# generic_midi_1.net
KiCad netlist of a schematic drawn in EAGLE
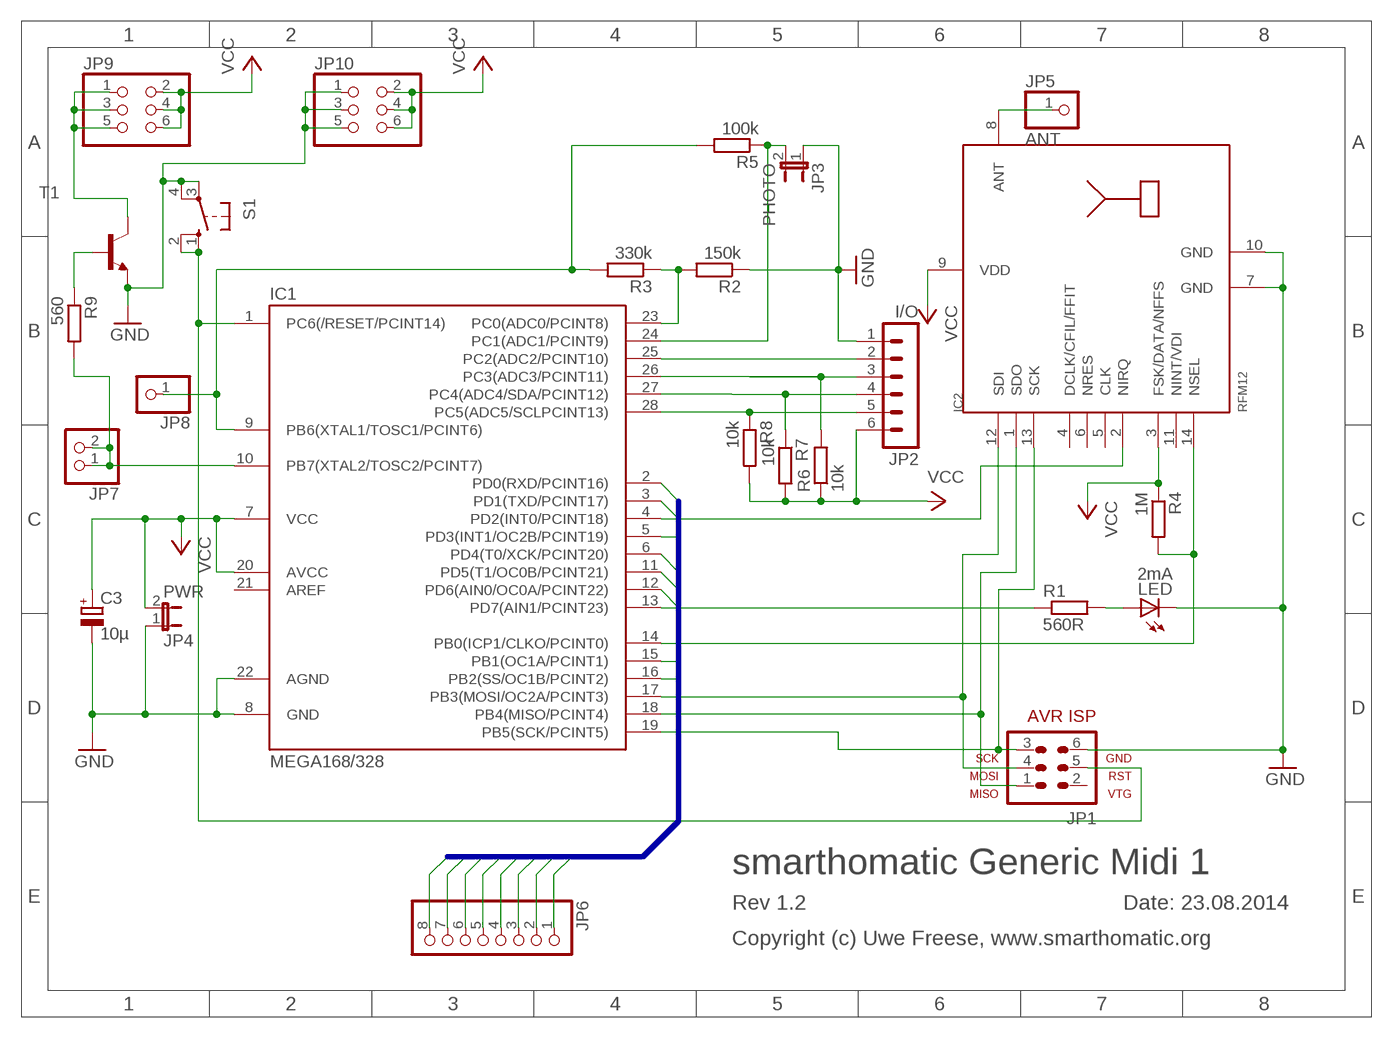
[diagram p0: schematic, sheet 1]

(export (version "E")
  (design (tool "Eeschema 10.0.6"))
  (components
    (comp (ref "C3")
      (value "10µ")
      (footprint "eagle-import:E1,8-4")
      (libsource (lib "eagle-import") (part "CPOL-EUE1.8-4"))
    )
    (comp (ref "IC1")
      (value "MEGA168/328")
      (footprint "eagle-import:DIL28-3")
      (libsource (lib "eagle-import") (part "MEGA48/88/168-PU"))
    )
    (comp (ref "IC2")
      (value "RFM12")
      (footprint "eagle-import:RFM")
      (libsource (lib "eagle-import") (part "RFM12"))
    )
    (comp (ref "JP1")
      (value "AVR-ISP-6")
      (footprint "eagle-import:AVR-ISP-6")
      (libsource (lib "eagle-import") (part "AVR-ISP-6"))
    )
    (comp (ref "JP2")
      (value "I/O")
      (footprint "eagle-import:MA06-1")
      (libsource (lib "eagle-import") (part "MA06-1"))
    )
    (comp (ref "JP3")
      (value "PHOTO")
      (footprint "eagle-import:JP1")
      (libsource (lib "eagle-import") (part "JP1E"))
    )
    (comp (ref "JP4")
      (value "PWR")
      (footprint "eagle-import:JP1")
      (libsource (lib "eagle-import") (part "JP1E"))
    )
    (comp (ref "JP5")
      (value "ANT")
      (footprint "eagle-import:1X01")
      (libsource (lib "eagle-import") (part "PINHD-1X1"))
    )
    (comp (ref "JP6")
      (value "PINHD-1X8")
      (footprint "eagle-import:1X08")
      (libsource (lib "eagle-import") (part "PINHD-1X8"))
    )
    (comp (ref "JP7")
      (value "PINHD-1X2")
      (footprint "eagle-import:1X02")
      (libsource (lib "eagle-import") (part "PINHD-1X2"))
    )
    (comp (ref "JP8")
      (value "PINHD-1X1")
      (footprint "eagle-import:1X01")
      (libsource (lib "eagle-import") (part "PINHD-1X1"))
    )
    (comp (ref "JP9")
      (value "PINHD-2X3")
      (footprint "eagle-import:2X03")
      (libsource (lib "eagle-import") (part "PINHD-2X3"))
    )
    (comp (ref "JP10")
      (value "PINHD-2X3")
      (footprint "eagle-import:2X03")
      (libsource (lib "eagle-import") (part "PINHD-2X3"))
    )
    (comp (ref "LED")
      (value "2mA")
      (footprint "eagle-import:LED3MM")
      (libsource (lib "eagle-import") (part "LED3MM"))
    )
    (comp (ref "R1")
      (value "560R")
      (footprint "eagle-import:0207_7")
      (libsource (lib "eagle-import") (part "R-EU_0207/7"))
    )
    (comp (ref "R2")
      (value "150k")
      (footprint "eagle-import:0207_7")
      (libsource (lib "eagle-import") (part "R-EU_0207/7"))
    )
    (comp (ref "R3")
      (value "330k")
      (footprint "eagle-import:0207_7")
      (libsource (lib "eagle-import") (part "R-EU_0207/7"))
    )
    (comp (ref "R4")
      (value "1M")
      (footprint "eagle-import:0207_7")
      (libsource (lib "eagle-import") (part "R-EU_0207/7"))
    )
    (comp (ref "R5")
      (value "100k")
      (footprint "eagle-import:0207_7")
      (libsource (lib "eagle-import") (part "R-EU_0207/7"))
    )
    (comp (ref "R6")
      (value "10k")
      (footprint "eagle-import:0207_7")
      (libsource (lib "eagle-import") (part "R-EU_0207/7"))
    )
    (comp (ref "R7")
      (value "10k")
      (footprint "eagle-import:0207_7")
      (libsource (lib "eagle-import") (part "R-EU_0207/7"))
    )
    (comp (ref "R8")
      (value "10k")
      (footprint "eagle-import:0207_7")
      (libsource (lib "eagle-import") (part "R-EU_0207/7"))
    )
    (comp (ref "R9")
      (value "560")
      (footprint "eagle-import:0207_7")
      (libsource (lib "eagle-import") (part "R-EU_0207/7"))
    )
    (comp (ref "S1")
      (value "10-XX")
      (footprint "eagle-import:B3F-10XX")
      (fields (field (name "MPN") "B3F-1000"))
      (libsource (lib "eagle-import") (part "10-XX"))
    )
    (comp (ref "T1")
      (value "BC547-NPN-TO92-CBE")
      (footprint "eagle-import:TO92-CBE")
      (libsource (lib "eagle-import") (part "-NPN-TO92-CBEBC547"))
    )
  )
  (nets
    (net (code "1") (name "/IO0") (class "Default")
      (node (ref "IC1") (pin "3") (pinfunction "PD1(TXD/PCINT17)_3") (pintype "bidirectional"))
      (node (ref "JP6") (pin "1") (pinfunction "1_1") (pintype "passive"))
    )
    (net (code "2") (name "/IO1") (class "Default")
      (node (ref "IC1") (pin "2") (pinfunction "PD0(RXD/PCINT16)_2") (pintype "bidirectional"))
      (node (ref "JP6") (pin "2") (pinfunction "2_2") (pintype "passive"))
    )
    (net (code "3") (name "/IO2") (class "Default")
      (node (ref "IC1") (pin "5") (pinfunction "PD3(INT1/OC2B/PCINT19)_5") (pintype "bidirectional"))
      (node (ref "JP6") (pin "3") (pinfunction "3_3") (pintype "passive"))
    )
    (net (code "4") (name "/IO3") (class "Default")
      (node (ref "IC1") (pin "6") (pinfunction "PD4(T0/XCK/PCINT20)_6") (pintype "bidirectional"))
      (node (ref "JP6") (pin "4") (pinfunction "4_4") (pintype "passive"))
    )
    (net (code "5") (name "/IO4") (class "Default")
      (node (ref "IC1") (pin "11") (pinfunction "PD5(T1/OC0B/PCINT21)_11") (pintype "bidirectional"))
      (node (ref "JP6") (pin "5") (pinfunction "5_5") (pintype "passive"))
    )
    (net (code "6") (name "/IO5") (class "Default")
      (node (ref "IC1") (pin "12") (pinfunction "PD6(AIN0/OC0A/PCINT22)_12") (pintype "bidirectional"))
      (node (ref "JP6") (pin "6") (pinfunction "6_6") (pintype "passive"))
    )
    (net (code "7") (name "/IO6") (class "Default")
      (node (ref "IC1") (pin "15") (pinfunction "PB1(OC1A/PCINT1)_15") (pintype "bidirectional"))
      (node (ref "JP6") (pin "7") (pinfunction "7_7") (pintype "passive"))
    )
    (net (code "8") (name "/IO7") (class "Default")
      (node (ref "IC1") (pin "16") (pinfunction "PB2(SS/OC1B/PCINT2)_16") (pintype "bidirectional"))
      (node (ref "JP6") (pin "8") (pinfunction "8_8") (pintype "passive"))
    )
    (net (code "9") (name "GND") (class "Default")
      (node (ref "C3") (pin "-") (pinfunction "-_-") (pintype "passive"))
      (node (ref "IC1") (pin "22") (pinfunction "AGND_22") (pintype "power_in"))
      (node (ref "IC1") (pin "8") (pinfunction "GND_8") (pintype "power_in"))
      (node (ref "IC2") (pin "10") (pinfunction "GND_10") (pintype "power_in"))
      (node (ref "IC2") (pin "7") (pinfunction "GND_7") (pintype "power_in"))
      (node (ref "JP1") (pin "6") (pinfunction "6_6") (pintype "passive"))
      (node (ref "JP10") (pin "1") (pinfunction "1_1") (pintype "passive"))
      (node (ref "JP10") (pin "3") (pinfunction "3_3") (pintype "passive"))
      (node (ref "JP10") (pin "5") (pinfunction "5_5") (pintype "passive"))
      (node (ref "JP2") (pin "1") (pinfunction "1_1") (pintype "passive"))
      (node (ref "JP3") (pin "1") (pinfunction "1_1") (pintype "passive"))
      (node (ref "JP4") (pin "1") (pinfunction "1_1") (pintype "passive"))
      (node (ref "LED") (pin "K") (pinfunction "C_K") (pintype "passive"))
      (node (ref "R2") (pin "1") (pinfunction "1_1") (pintype "passive"))
      (node (ref "S1") (pin "3") (pinfunction "P_3") (pintype "passive"))
      (node (ref "S1") (pin "4") (pinfunction "P1_4") (pintype "passive"))
      (node (ref "T1") (pin "E") (pinfunction "E_E") (pintype "passive"))
    )
    (net (code "10") (name "Net-(IC1-PB0(ICP1{slash}CLKO{slash}PCINT0))") (class "Default")
      (node (ref "IC1") (pin "14") (pinfunction "PB0(ICP1/CLKO/PCINT0)_14") (pintype "bidirectional"))
      (node (ref "IC2") (pin "14") (pinfunction "NSEL_14") (pintype "bidirectional"))
      (node (ref "R4") (pin "2") (pinfunction "2_2") (pintype "passive"))
    )
    (net (code "11") (name "Net-(IC1-PB3(MOSI{slash}OC2A{slash}PCINT3))") (class "Default")
      (node (ref "IC1") (pin "17") (pinfunction "PB3(MOSI/OC2A/PCINT3)_17") (pintype "bidirectional"))
      (node (ref "IC2") (pin "12") (pinfunction "SDI_12") (pintype "bidirectional"))
      (node (ref "JP1") (pin "4") (pinfunction "4_4") (pintype "passive"))
    )
    (net (code "12") (name "Net-(IC1-PB4(MISO{slash}PCINT4))") (class "Default")
      (node (ref "IC1") (pin "18") (pinfunction "PB4(MISO/PCINT4)_18") (pintype "bidirectional"))
      (node (ref "IC2") (pin "1") (pinfunction "SDO_1") (pintype "bidirectional"))
      (node (ref "JP1") (pin "1") (pinfunction "1_1") (pintype "passive"))
    )
    (net (code "13") (name "Net-(IC1-PB5(SCK{slash}PCINT5))") (class "Default")
      (node (ref "IC1") (pin "19") (pinfunction "PB5(SCK/PCINT5)_19") (pintype "bidirectional"))
      (node (ref "IC2") (pin "13") (pinfunction "SCK_13") (pintype "bidirectional"))
      (node (ref "JP1") (pin "3") (pinfunction "3_3") (pintype "passive"))
    )
    (net (code "14") (name "Net-(IC1-PB6(XTAL1{slash}TOSC1{slash}PCINT6))") (class "Default")
      (node (ref "IC1") (pin "9") (pinfunction "PB6(XTAL1/TOSC1/PCINT6)_9") (pintype "bidirectional"))
      (node (ref "JP8") (pin "1") (pinfunction "1_1") (pintype "passive"))
      (node (ref "R3") (pin "2") (pinfunction "2_2") (pintype "passive"))
      (node (ref "R5") (pin "2") (pinfunction "2_2") (pintype "passive"))
    )
    (net (code "15") (name "Net-(IC1-PB7(XTAL2{slash}TOSC2{slash}PCINT7))") (class "Default")
      (node (ref "IC1") (pin "10") (pinfunction "PB7(XTAL2/TOSC2/PCINT7)_10") (pintype "bidirectional"))
      (node (ref "JP7") (pin "1") (pinfunction "1_1") (pintype "passive"))
      (node (ref "JP7") (pin "2") (pinfunction "2_2") (pintype "passive"))
      (node (ref "R9") (pin "2") (pinfunction "2_2") (pintype "passive"))
    )
    (net (code "16") (name "Net-(IC1-PC0(ADC0{slash}PCINT8))") (class "Default")
      (node (ref "IC1") (pin "23") (pinfunction "PC0(ADC0/PCINT8)_23") (pintype "bidirectional"))
      (node (ref "R2") (pin "2") (pinfunction "2_2") (pintype "passive"))
      (node (ref "R3") (pin "1") (pinfunction "1_1") (pintype "passive"))
    )
    (net (code "17") (name "Net-(IC1-PC1(ADC1{slash}PCINT9))") (class "Default")
      (node (ref "IC1") (pin "24") (pinfunction "PC1(ADC1/PCINT9)_24") (pintype "bidirectional"))
      (node (ref "JP3") (pin "2") (pinfunction "2_2") (pintype "passive"))
      (node (ref "R5") (pin "1") (pinfunction "1_1") (pintype "passive"))
    )
    (net (code "18") (name "Net-(IC1-PC2(ADC2{slash}PCINT10))") (class "Default")
      (node (ref "IC1") (pin "25") (pinfunction "PC2(ADC2/PCINT10)_25") (pintype "bidirectional"))
      (node (ref "JP2") (pin "2") (pinfunction "2_2") (pintype "passive"))
    )
    (net (code "19") (name "Net-(IC1-PC3(ADC3{slash}PCINT11))") (class "Default")
      (node (ref "IC1") (pin "26") (pinfunction "PC3(ADC3/PCINT11)_26") (pintype "bidirectional"))
      (node (ref "JP2") (pin "3") (pinfunction "3_3") (pintype "passive"))
      (node (ref "R6") (pin "2") (pinfunction "2_2") (pintype "passive"))
    )
    (net (code "20") (name "Net-(IC1-PC4(ADC4{slash}SDA{slash}PCINT12))") (class "Default")
      (node (ref "IC1") (pin "27") (pinfunction "PC4(ADC4/SDA/PCINT12)_27") (pintype "bidirectional"))
      (node (ref "JP2") (pin "4") (pinfunction "4_4") (pintype "passive"))
      (node (ref "R7") (pin "1") (pinfunction "1_1") (pintype "passive"))
    )
    (net (code "21") (name "Net-(IC1-PC5(ADC5{slash}SCLPCINT13))") (class "Default")
      (node (ref "IC1") (pin "28") (pinfunction "PC5(ADC5/SCLPCINT13)_28") (pintype "bidirectional"))
      (node (ref "JP2") (pin "5") (pinfunction "5_5") (pintype "passive"))
      (node (ref "R8") (pin "1") (pinfunction "1_1") (pintype "passive"))
    )
    (net (code "22") (name "Net-(IC1-PC6({slash}RESET{slash}PCINT14))") (class "Default")
      (node (ref "IC1") (pin "1") (pinfunction "PC6(/RESET/PCINT14)_1") (pintype "bidirectional"))
      (node (ref "JP1") (pin "5") (pinfunction "5_5") (pintype "passive"))
      (node (ref "S1") (pin "1") (pinfunction "S_1") (pintype "passive"))
      (node (ref "S1") (pin "2") (pinfunction "S1_2") (pintype "passive"))
    )
    (net (code "23") (name "Net-(IC1-PD2(INT0{slash}PCINT18))") (class "Default")
      (node (ref "IC1") (pin "4") (pinfunction "PD2(INT0/PCINT18)_4") (pintype "bidirectional"))
      (node (ref "IC2") (pin "2") (pinfunction "NIRQ_2") (pintype "bidirectional"))
    )
    (net (code "24") (name "Net-(IC1-PD7(AIN1{slash}PCINT23))") (class "Default")
      (node (ref "IC1") (pin "13") (pinfunction "PD7(AIN1/PCINT23)_13") (pintype "bidirectional"))
      (node (ref "R1") (pin "1") (pinfunction "1_1") (pintype "passive"))
    )
    (net (code "25") (name "Net-(IC2-ANT)") (class "Default")
      (node (ref "IC2") (pin "8") (pinfunction "ANT_8") (pintype "output"))
      (node (ref "JP5") (pin "1") (pinfunction "1_1") (pintype "passive"))
    )
    (net (code "26") (name "Net-(JP9-Pad1)") (class "Default")
      (node (ref "JP9") (pin "1") (pinfunction "1_1") (pintype "passive"))
      (node (ref "JP9") (pin "3") (pinfunction "3_3") (pintype "passive"))
      (node (ref "JP9") (pin "5") (pinfunction "5_5") (pintype "passive"))
      (node (ref "T1") (pin "C") (pinfunction "C_C") (pintype "passive"))
    )
    (net (code "27") (name "Net-(LED-PadA)") (class "Default")
      (node (ref "LED") (pin "A") (pinfunction "A_A") (pintype "passive"))
      (node (ref "R1") (pin "2") (pinfunction "2_2") (pintype "passive"))
    )
    (net (code "28") (name "Net-(R9-Pad1)") (class "Default")
      (node (ref "R9") (pin "1") (pinfunction "1_1") (pintype "passive"))
      (node (ref "T1") (pin "B") (pinfunction "B_B") (pintype "passive"))
    )
    (net (code "29") (name "VCC") (class "Default")
      (node (ref "C3") (pin "+") (pinfunction "+_+") (pintype "passive"))
      (node (ref "IC1") (pin "20") (pinfunction "AVCC_20") (pintype "passive"))
      (node (ref "IC1") (pin "7") (pinfunction "VCC_7") (pintype "power_in"))
      (node (ref "IC2") (pin "3") (pinfunction "FSK/DATA/NFFS_3") (pintype "bidirectional"))
      (node (ref "IC2") (pin "9") (pinfunction "VDD_9") (pintype "power_in"))
      (node (ref "JP10") (pin "2") (pinfunction "2_2") (pintype "passive"))
      (node (ref "JP10") (pin "4") (pinfunction "4_4") (pintype "passive"))
      (node (ref "JP10") (pin "6") (pinfunction "6_6") (pintype "passive"))
      (node (ref "JP2") (pin "6") (pinfunction "6_6") (pintype "passive"))
      (node (ref "JP4") (pin "2") (pinfunction "2_2") (pintype "passive"))
      (node (ref "JP9") (pin "2") (pinfunction "2_2") (pintype "passive"))
      (node (ref "JP9") (pin "4") (pinfunction "4_4") (pintype "passive"))
      (node (ref "JP9") (pin "6") (pinfunction "6_6") (pintype "passive"))
      (node (ref "R4") (pin "1") (pinfunction "1_1") (pintype "passive"))
      (node (ref "R6") (pin "1") (pinfunction "1_1") (pintype "passive"))
      (node (ref "R7") (pin "2") (pinfunction "2_2") (pintype "passive"))
      (node (ref "R8") (pin "2") (pinfunction "2_2") (pintype "passive"))
    )
    (net (code "30") (name "unconnected-(IC1-AREF-Pad21)") (class "Default")
      (node (ref "IC1") (pin "21") (pinfunction "AREF_21") (pintype "passive"))
    )
    (net (code "31") (name "unconnected-(IC2-CLK-Pad5)") (class "Default")
      (node (ref "IC2") (pin "5") (pinfunction "CLK_5") (pintype "bidirectional"))
    )
    (net (code "32") (name "unconnected-(IC2-DCLK{slash}CFIL{slash}FFIT-Pad4)") (class "Default")
      (node (ref "IC2") (pin "4") (pinfunction "DCLK/CFIL/FFIT_4") (pintype "bidirectional"))
    )
    (net (code "33") (name "unconnected-(IC2-NINT{slash}VDI-Pad11)") (class "Default")
      (node (ref "IC2") (pin "11") (pinfunction "NINT/VDI_11") (pintype "bidirectional"))
    )
    (net (code "34") (name "unconnected-(IC2-NRES-Pad6)") (class "Default")
      (node (ref "IC2") (pin "6") (pinfunction "NRES_6") (pintype "bidirectional"))
    )
    (net (code "35") (name "unconnected-(JP1-Pad2)") (class "Default")
      (node (ref "JP1") (pin "2") (pinfunction "2_2") (pintype "passive"))
    )
  )
)
